# waga_can.net
KiCad netlist of a schematic drawn in EAGLE
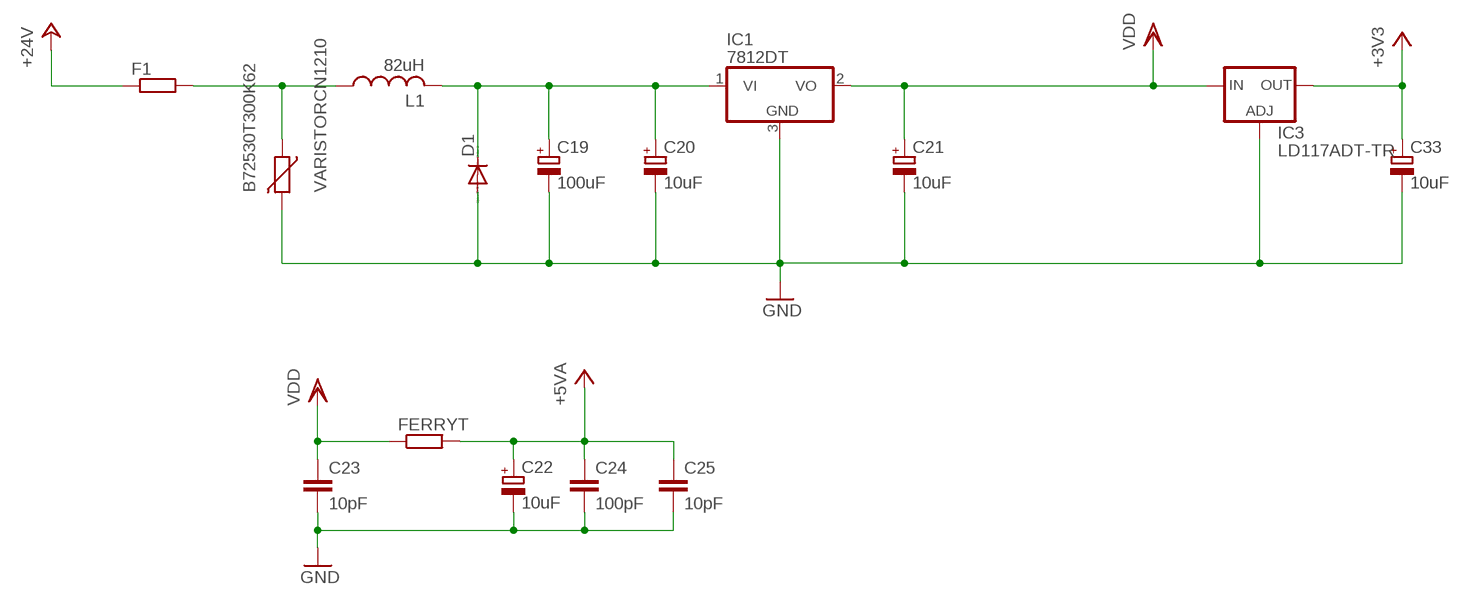
[diagram p0: schematic, sheet 1]
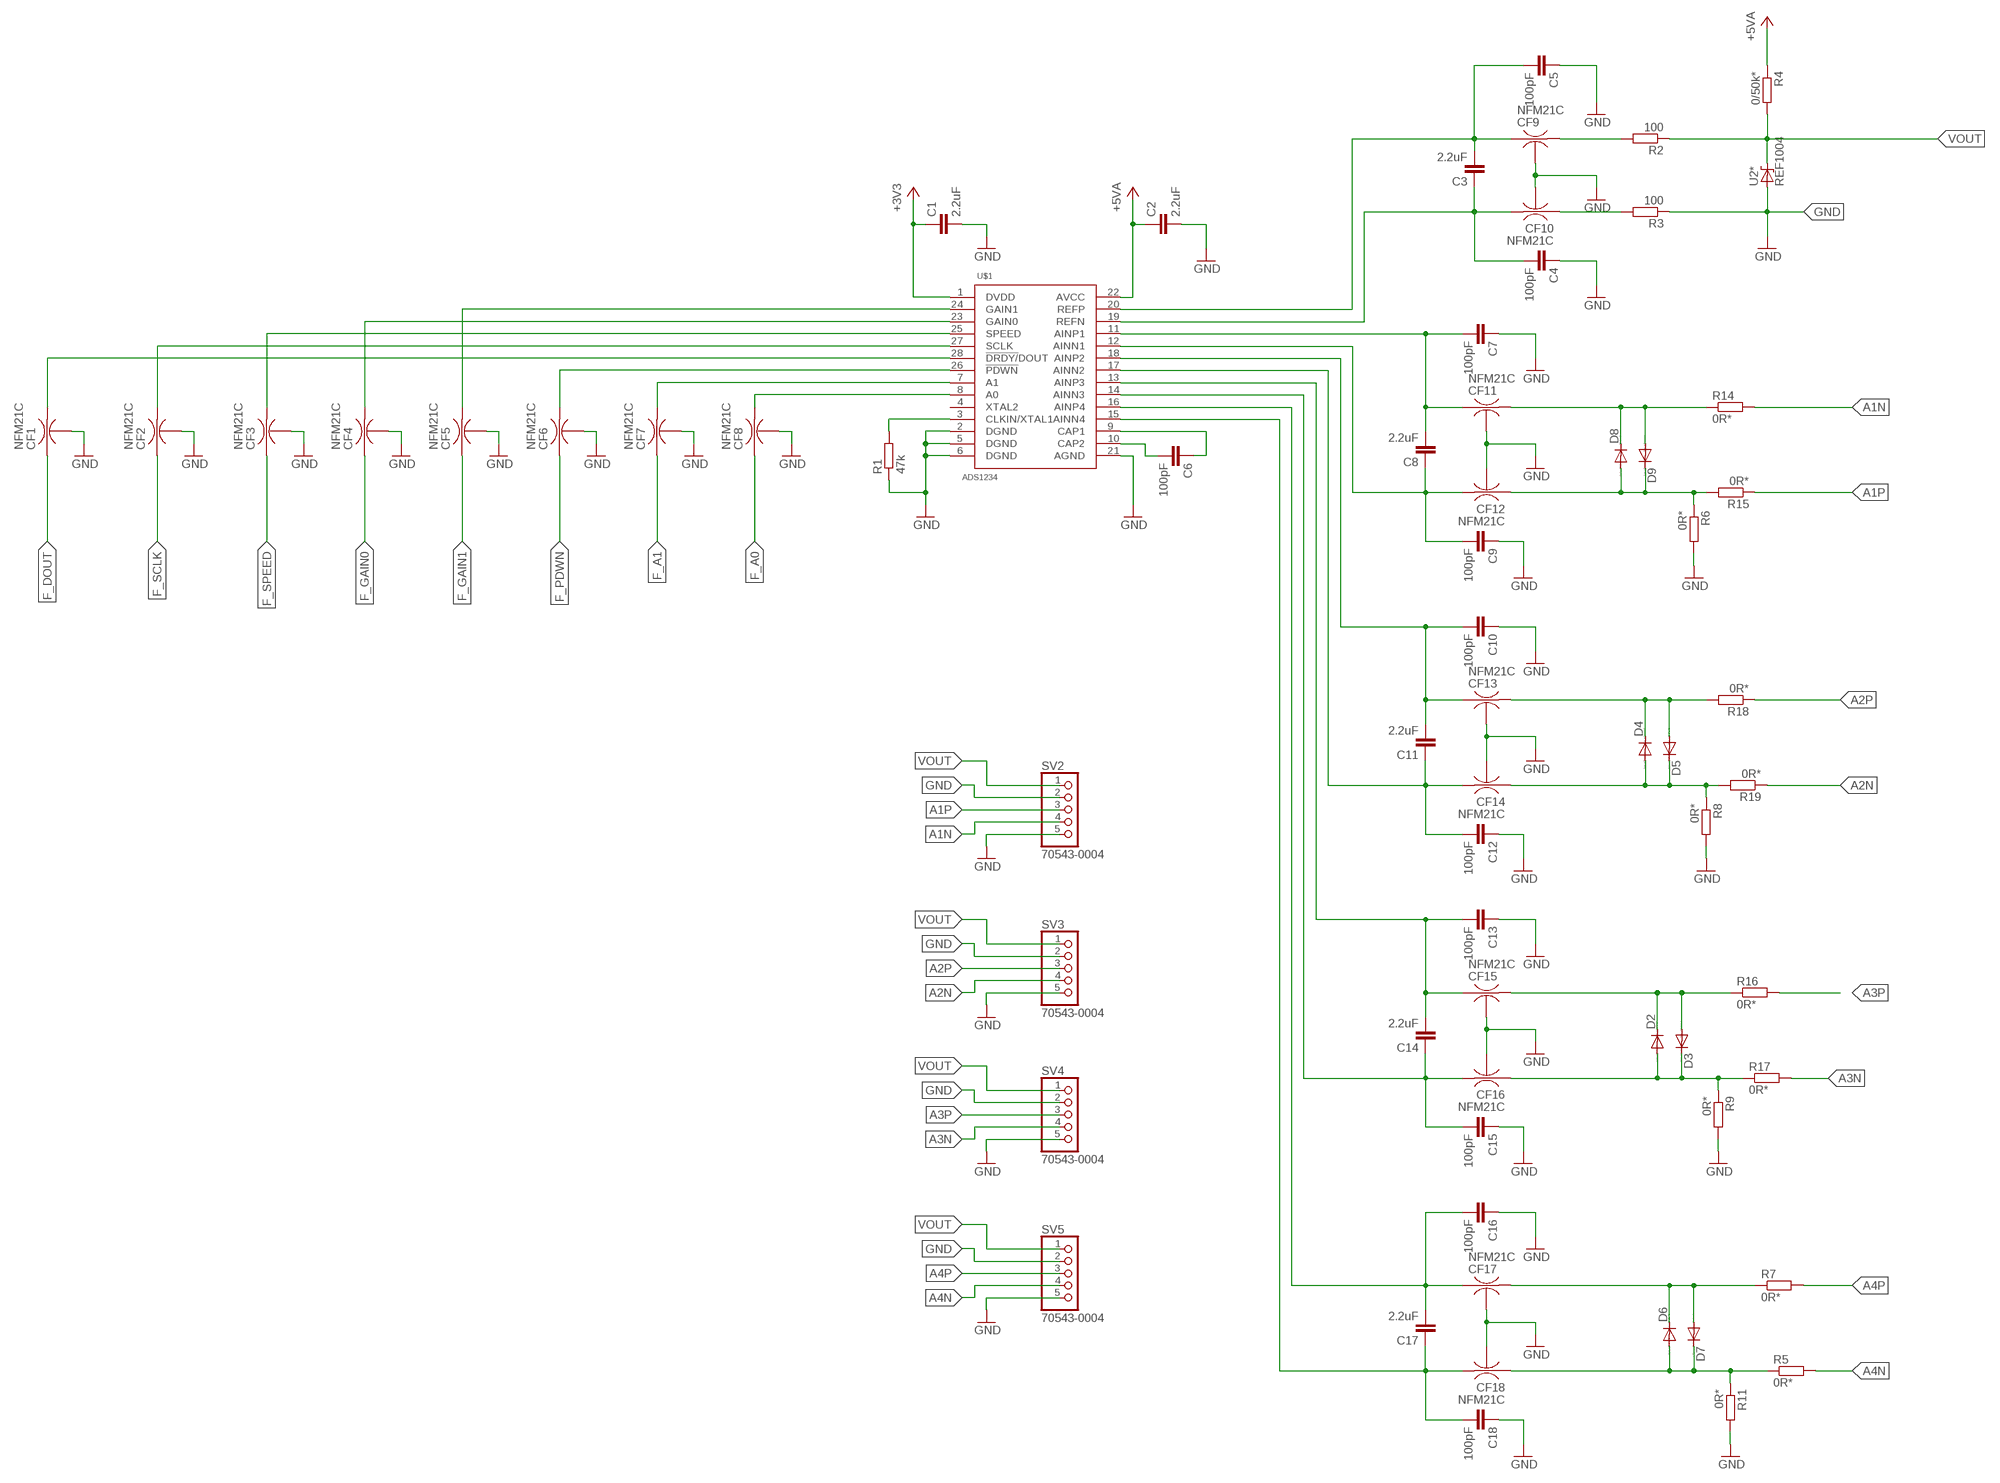
[diagram p1: schematic, sheet 2, part 1 of 2]
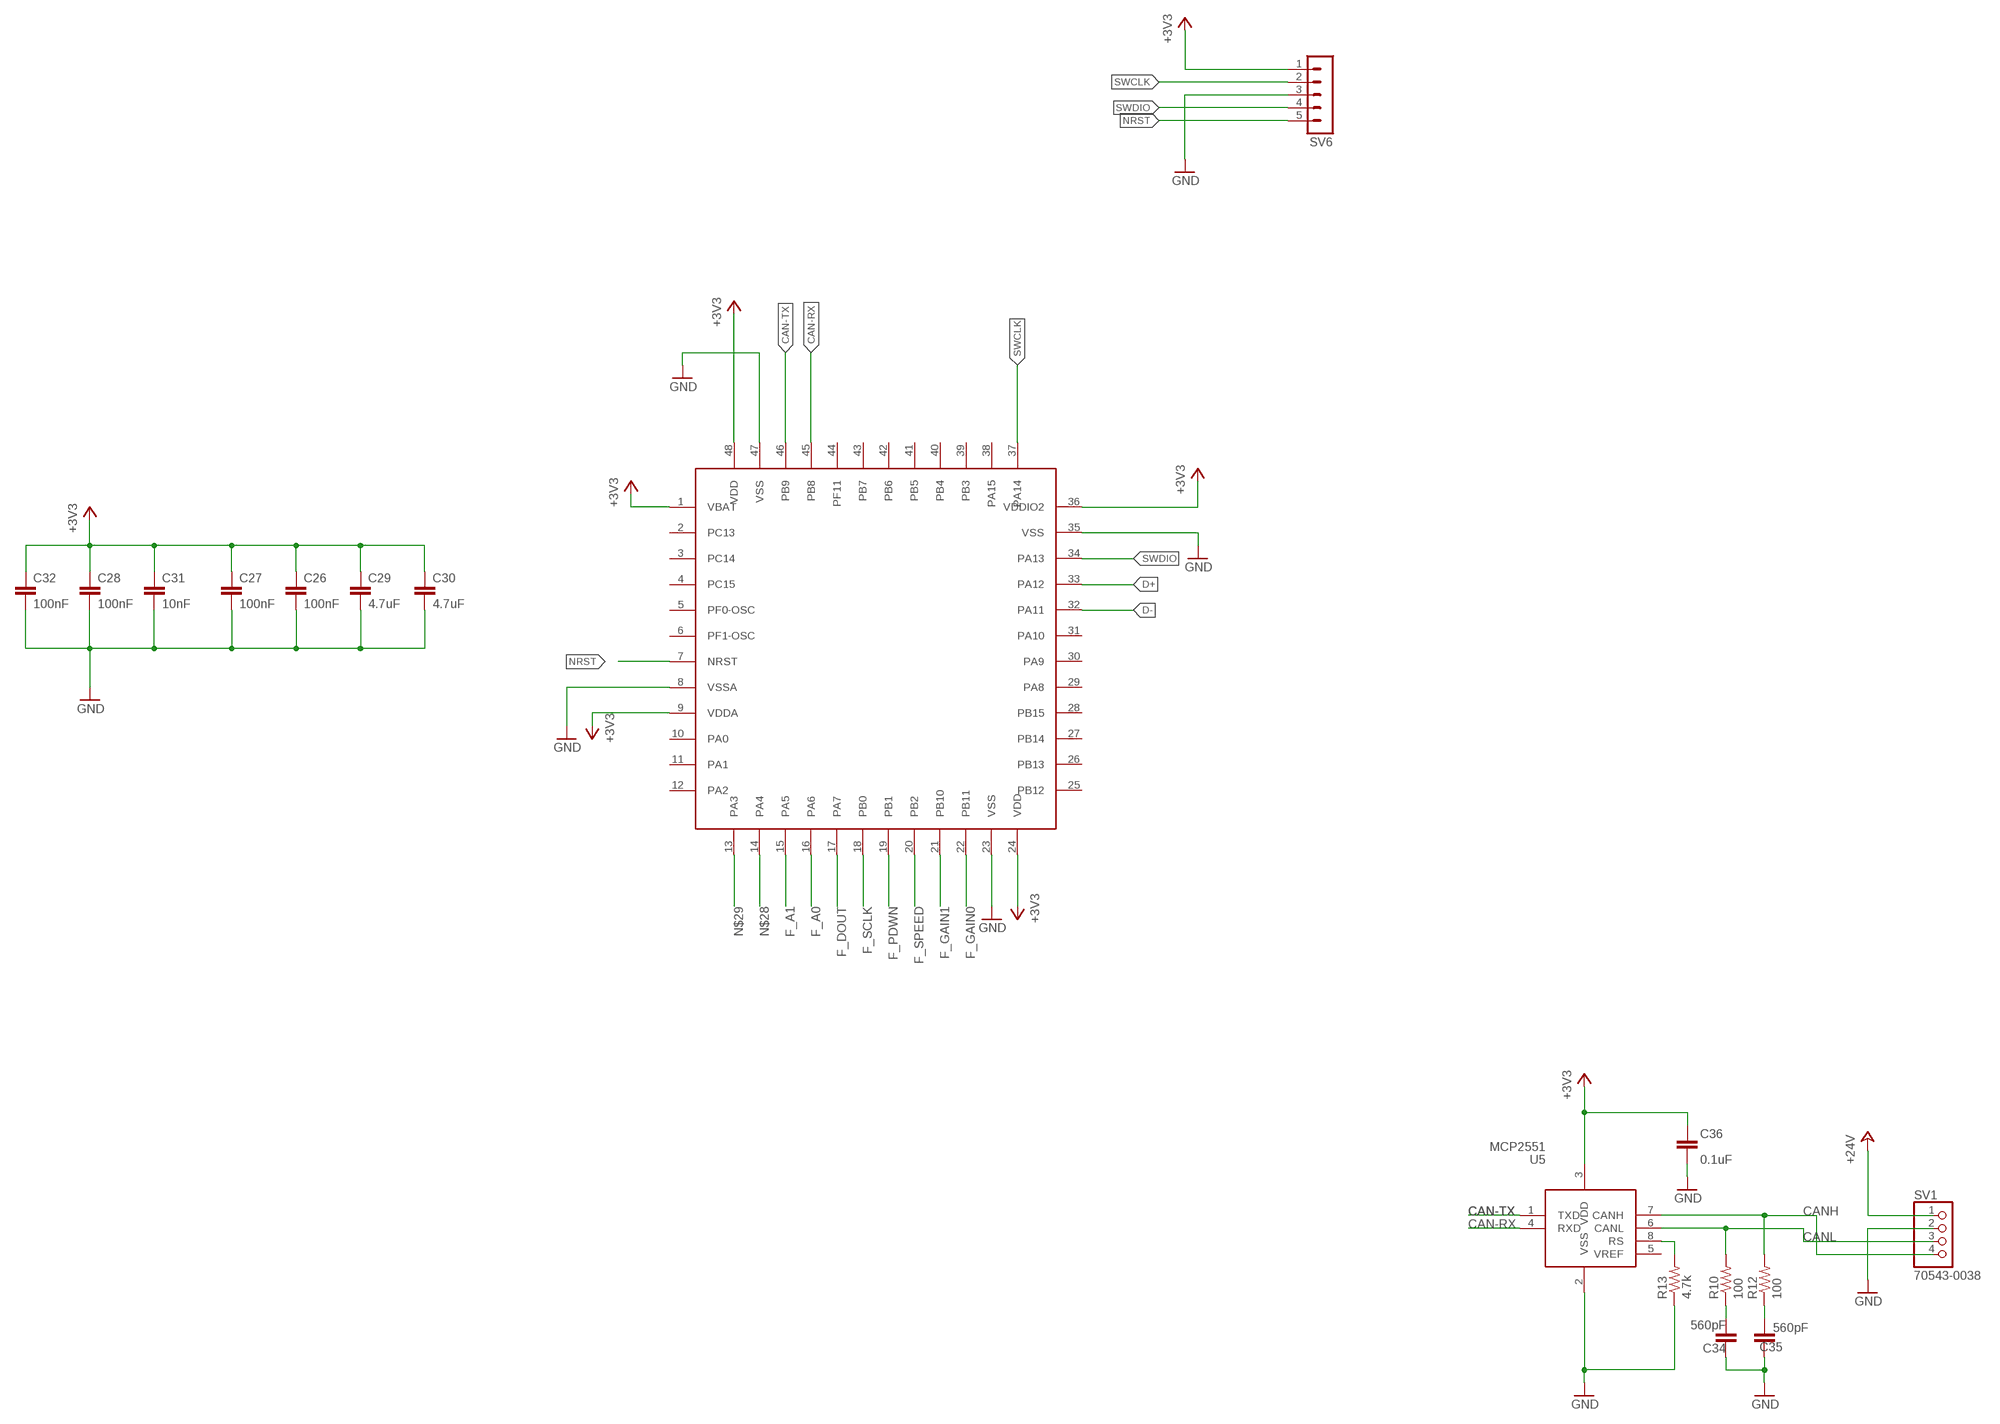
[diagram p2: schematic, sheet 2, part 2 of 2]

(export (version "E")
  (design (tool "Eeschema 10.0.6"))
  (components
    (comp (ref "C1")
      (value "2.2uF")
      (footprint "eagle-import:C0805K")
      (libsource (lib "eagle-import") (part "C-EUC0805K"))
    )
    (comp (ref "C2")
      (value "2.2uF")
      (footprint "eagle-import:C0805K")
      (libsource (lib "eagle-import") (part "C-EUC0805K"))
    )
    (comp (ref "C3")
      (value "2.2uF")
      (footprint "eagle-import:C0805K")
      (libsource (lib "eagle-import") (part "C-EUC0805K"))
    )
    (comp (ref "C4")
      (value "100pF")
      (footprint "eagle-import:C0805K")
      (libsource (lib "eagle-import") (part "C-EUC0805K"))
    )
    (comp (ref "C5")
      (value "100pF")
      (footprint "eagle-import:C0805K")
      (libsource (lib "eagle-import") (part "C-EUC0805K"))
    )
    (comp (ref "C6")
      (value "100pF")
      (footprint "eagle-import:C0805K")
      (libsource (lib "eagle-import") (part "C-EUC0805K"))
    )
    (comp (ref "C7")
      (value "100pF")
      (footprint "eagle-import:C0805K")
      (libsource (lib "eagle-import") (part "C-EUC0805K"))
    )
    (comp (ref "C8")
      (value "2.2uF")
      (footprint "eagle-import:C0805K")
      (libsource (lib "eagle-import") (part "C-EUC0805K"))
    )
    (comp (ref "C9")
      (value "100pF")
      (footprint "eagle-import:C0805K")
      (libsource (lib "eagle-import") (part "C-EUC0805K"))
    )
    (comp (ref "C10")
      (value "100pF")
      (footprint "eagle-import:C0805K")
      (libsource (lib "eagle-import") (part "C-EUC0805K"))
    )
    (comp (ref "C11")
      (value "2.2uF")
      (footprint "eagle-import:C0805K")
      (libsource (lib "eagle-import") (part "C-EUC0805K"))
    )
    (comp (ref "C12")
      (value "100pF")
      (footprint "eagle-import:C0805K")
      (libsource (lib "eagle-import") (part "C-EUC0805K"))
    )
    (comp (ref "C13")
      (value "100pF")
      (footprint "eagle-import:C0805K")
      (libsource (lib "eagle-import") (part "C-EUC0805K"))
    )
    (comp (ref "C14")
      (value "2.2uF")
      (footprint "eagle-import:C0805K")
      (libsource (lib "eagle-import") (part "C-EUC0805K"))
    )
    (comp (ref "C15")
      (value "100pF")
      (footprint "eagle-import:C0805K")
      (libsource (lib "eagle-import") (part "C-EUC0805K"))
    )
    (comp (ref "C16")
      (value "100pF")
      (footprint "eagle-import:C0805K")
      (libsource (lib "eagle-import") (part "C-EUC0805K"))
    )
    (comp (ref "C17")
      (value "2.2uF")
      (footprint "eagle-import:C0805K")
      (libsource (lib "eagle-import") (part "C-EUC0805K"))
    )
    (comp (ref "C18")
      (value "100pF")
      (footprint "eagle-import:C0805K")
      (libsource (lib "eagle-import") (part "C-EUC0805K"))
    )
    (comp (ref "C26")
      (value "100nF")
      (footprint "eagle-import:C0603")
      (libsource (lib "eagle-import") (part "C-EUC0603"))
    )
    (comp (ref "C27")
      (value "100nF")
      (footprint "eagle-import:C0603")
      (libsource (lib "eagle-import") (part "C-EUC0603"))
    )
    (comp (ref "C28")
      (value "100nF")
      (footprint "eagle-import:C0603")
      (libsource (lib "eagle-import") (part "C-EUC0603"))
    )
    (comp (ref "C29")
      (value "4.7uF")
      (footprint "eagle-import:C0603")
      (libsource (lib "eagle-import") (part "C-EUC0603"))
    )
    (comp (ref "C30")
      (value "4.7uF")
      (footprint "eagle-import:C0603")
      (libsource (lib "eagle-import") (part "C-EUC0603"))
    )
    (comp (ref "C31")
      (value "10nF")
      (footprint "eagle-import:C0603")
      (libsource (lib "eagle-import") (part "C-EUC0603"))
    )
    (comp (ref "C32")
      (value "100nF")
      (footprint "eagle-import:C0603")
      (libsource (lib "eagle-import") (part "C-EUC0603"))
    )
    (comp (ref "C34")
      (value "560pF")
      (footprint "eagle-import:0603-CAP")
      (libsource (lib "eagle-import") (part "CAP0603-CAP"))
    )
    (comp (ref "C35")
      (value "560pF")
      (footprint "eagle-import:0603-CAP")
      (libsource (lib "eagle-import") (part "CAP0603-CAP"))
    )
    (comp (ref "C36")
      (value "0.1uF")
      (footprint "eagle-import:0603-CAP")
      (libsource (lib "eagle-import") (part "CAP0603-CAP"))
    )
    (comp (ref "CF1")
      (value "NFM21C")
      (footprint "eagle-import:NFM21C")
      (fields (field (name "MPN") "NFM21CC102R1H3D"))
      (libsource (lib "eagle-import") (part "NFM21C"))
    )
    (comp (ref "CF2")
      (value "NFM21C")
      (footprint "eagle-import:NFM21C")
      (fields (field (name "MPN") "NFM21CC102R1H3D"))
      (libsource (lib "eagle-import") (part "NFM21C"))
    )
    (comp (ref "CF3")
      (value "NFM21C")
      (footprint "eagle-import:NFM21C")
      (fields (field (name "MPN") "NFM21CC102R1H3D"))
      (libsource (lib "eagle-import") (part "NFM21C"))
    )
    (comp (ref "CF4")
      (value "NFM21C")
      (footprint "eagle-import:NFM21C")
      (fields (field (name "MPN") "NFM21CC102R1H3D"))
      (libsource (lib "eagle-import") (part "NFM21C"))
    )
    (comp (ref "CF5")
      (value "NFM21C")
      (footprint "eagle-import:NFM21C")
      (fields (field (name "MPN") "NFM21CC102R1H3D"))
      (libsource (lib "eagle-import") (part "NFM21C"))
    )
    (comp (ref "CF6")
      (value "NFM21C")
      (footprint "eagle-import:NFM21C")
      (fields (field (name "MPN") "NFM21CC102R1H3D"))
      (libsource (lib "eagle-import") (part "NFM21C"))
    )
    (comp (ref "CF7")
      (value "NFM21C")
      (footprint "eagle-import:NFM21C")
      (fields (field (name "MPN") "NFM21CC102R1H3D"))
      (libsource (lib "eagle-import") (part "NFM21C"))
    )
    (comp (ref "CF8")
      (value "NFM21C")
      (footprint "eagle-import:NFM21C")
      (fields (field (name "MPN") "NFM21CC102R1H3D"))
      (libsource (lib "eagle-import") (part "NFM21C"))
    )
    (comp (ref "CF9")
      (value "NFM21C")
      (footprint "eagle-import:NFM21C")
      (fields (field (name "MPN") "NFM21CC102R1H3D"))
      (libsource (lib "eagle-import") (part "NFM21C"))
    )
    (comp (ref "CF10")
      (value "NFM21C")
      (footprint "eagle-import:NFM21C")
      (fields (field (name "MPN") "NFM21CC102R1H3D"))
      (libsource (lib "eagle-import") (part "NFM21C"))
    )
    (comp (ref "CF11")
      (value "NFM21C")
      (footprint "eagle-import:NFM21C")
      (fields (field (name "MPN") "NFM21CC102R1H3D"))
      (libsource (lib "eagle-import") (part "NFM21C"))
    )
    (comp (ref "CF12")
      (value "NFM21C")
      (footprint "eagle-import:NFM21C")
      (fields (field (name "MPN") "NFM21CC102R1H3D"))
      (libsource (lib "eagle-import") (part "NFM21C"))
    )
    (comp (ref "CF13")
      (value "NFM21C")
      (footprint "eagle-import:NFM21C")
      (fields (field (name "MPN") "NFM21CC102R1H3D"))
      (libsource (lib "eagle-import") (part "NFM21C"))
    )
    (comp (ref "CF14")
      (value "NFM21C")
      (footprint "eagle-import:NFM21C")
      (fields (field (name "MPN") "NFM21CC102R1H3D"))
      (libsource (lib "eagle-import") (part "NFM21C"))
    )
    (comp (ref "CF15")
      (value "NFM21C")
      (footprint "eagle-import:NFM21C")
      (fields (field (name "MPN") "NFM21CC102R1H3D"))
      (libsource (lib "eagle-import") (part "NFM21C"))
    )
    (comp (ref "CF16")
      (value "NFM21C")
      (footprint "eagle-import:NFM21C")
      (fields (field (name "MPN") "NFM21CC102R1H3D"))
      (libsource (lib "eagle-import") (part "NFM21C"))
    )
    (comp (ref "CF17")
      (value "NFM21C")
      (footprint "eagle-import:NFM21C")
      (fields (field (name "MPN") "NFM21CC102R1H3D"))
      (libsource (lib "eagle-import") (part "NFM21C"))
    )
    (comp (ref "CF18")
      (value "NFM21C")
      (footprint "eagle-import:NFM21C")
      (fields (field (name "MPN") "NFM21CC102R1H3D"))
      (libsource (lib "eagle-import") (part "NFM21C"))
    )
    (comp (ref "D2")
      (value "DIODE-MICROMELF-W")
      (footprint "eagle-import:MICROMELF-W")
      (libsource (lib "eagle-import") (part "DIODE-MICROMELF-W"))
    )
    (comp (ref "D3")
      (value "DIODE-MICROMELF-W")
      (footprint "eagle-import:MICROMELF-W")
      (libsource (lib "eagle-import") (part "DIODE-MICROMELF-W"))
    )
    (comp (ref "D4")
      (value "DIODE-MICROMELF-W")
      (footprint "eagle-import:MICROMELF-W")
      (libsource (lib "eagle-import") (part "DIODE-MICROMELF-W"))
    )
    (comp (ref "D5")
      (value "DIODE-MICROMELF-W")
      (footprint "eagle-import:MICROMELF-W")
      (libsource (lib "eagle-import") (part "DIODE-MICROMELF-W"))
    )
    (comp (ref "D6")
      (value "DIODE-MICROMELF-W")
      (footprint "eagle-import:MICROMELF-W")
      (libsource (lib "eagle-import") (part "DIODE-MICROMELF-W"))
    )
    (comp (ref "D7")
      (value "DIODE-MICROMELF-W")
      (footprint "eagle-import:MICROMELF-W")
      (libsource (lib "eagle-import") (part "DIODE-MICROMELF-W"))
    )
    (comp (ref "D8")
      (value "DIODE-MICROMELF-W")
      (footprint "eagle-import:MICROMELF-W")
      (libsource (lib "eagle-import") (part "DIODE-MICROMELF-W"))
    )
    (comp (ref "D9")
      (value "DIODE-MICROMELF-W")
      (footprint "eagle-import:MICROMELF-W")
      (libsource (lib "eagle-import") (part "DIODE-MICROMELF-W"))
    )
    (comp (ref "R1")
      (value "47k")
      (footprint "eagle-import:R0805")
      (libsource (lib "eagle-import") (part "R-EU_R0805"))
    )
    (comp (ref "R2")
      (value "100")
      (footprint "eagle-import:R0805")
      (libsource (lib "eagle-import") (part "R-EU_R0805"))
    )
    (comp (ref "R3")
      (value "100")
      (footprint "eagle-import:R0805")
      (libsource (lib "eagle-import") (part "R-EU_R0805"))
    )
    (comp (ref "R4")
      (value "0/50k*")
      (footprint "eagle-import:R0805")
      (libsource (lib "eagle-import") (part "R-EU_R0805"))
    )
    (comp (ref "R5")
      (value "0R*")
      (footprint "eagle-import:R0603")
      (libsource (lib "eagle-import") (part "R-EU_R0603"))
    )
    (comp (ref "R6")
      (value "0R*")
      (footprint "eagle-import:R0603")
      (libsource (lib "eagle-import") (part "R-EU_R0603"))
    )
    (comp (ref "R7")
      (value "0R*")
      (footprint "eagle-import:R0603")
      (libsource (lib "eagle-import") (part "R-EU_R0603"))
    )
    (comp (ref "R8")
      (value "0R*")
      (footprint "eagle-import:R0603")
      (libsource (lib "eagle-import") (part "R-EU_R0603"))
    )
    (comp (ref "R9")
      (value "0R*")
      (footprint "eagle-import:R0603")
      (libsource (lib "eagle-import") (part "R-EU_R0603"))
    )
    (comp (ref "R10")
      (value "100")
      (footprint "eagle-import:0603-RES")
      (libsource (lib "eagle-import") (part "RESISTOR0603-RES"))
    )
    (comp (ref "R11")
      (value "0R*")
      (footprint "eagle-import:R0603")
      (libsource (lib "eagle-import") (part "R-EU_R0603"))
    )
    (comp (ref "R12")
      (value "100")
      (footprint "eagle-import:0603-RES")
      (libsource (lib "eagle-import") (part "RESISTOR0603-RES"))
    )
    (comp (ref "R13")
      (value "4.7k")
      (footprint "eagle-import:0603-RES")
      (libsource (lib "eagle-import") (part "RESISTOR0603-RES"))
    )
    (comp (ref "R14")
      (value "0R*")
      (footprint "eagle-import:R0603")
      (libsource (lib "eagle-import") (part "R-EU_R0603"))
    )
    (comp (ref "R15")
      (value "0R*")
      (footprint "eagle-import:R0603")
      (libsource (lib "eagle-import") (part "R-EU_R0603"))
    )
    (comp (ref "R16")
      (value "0R*")
      (footprint "eagle-import:R0603")
      (libsource (lib "eagle-import") (part "R-EU_R0603"))
    )
    (comp (ref "R17")
      (value "0R*")
      (footprint "eagle-import:R0603")
      (libsource (lib "eagle-import") (part "R-EU_R0603"))
    )
    (comp (ref "R18")
      (value "0R*")
      (footprint "eagle-import:R0603")
      (libsource (lib "eagle-import") (part "R-EU_R0603"))
    )
    (comp (ref "R19")
      (value "0R*")
      (footprint "eagle-import:R0603")
      (libsource (lib "eagle-import") (part "R-EU_R0603"))
    )
    (comp (ref "SV1")
      (value "70543-0038")
      (footprint "eagle-import:70543-0038")
      (libsource (lib "eagle-import") (part "70543-0038"))
    )
    (comp (ref "SV2")
      (value "70543-0004")
      (footprint "eagle-import:70543-0004")
      (libsource (lib "eagle-import") (part "70543-0004"))
    )
    (comp (ref "SV3")
      (value "70543-0004")
      (footprint "eagle-import:70543-0004")
      (libsource (lib "eagle-import") (part "70543-0004"))
    )
    (comp (ref "SV4")
      (value "70543-0004")
      (footprint "eagle-import:70543-0004")
      (libsource (lib "eagle-import") (part "70543-0004"))
    )
    (comp (ref "SV5")
      (value "70543-0004")
      (footprint "eagle-import:70543-0004")
      (libsource (lib "eagle-import") (part "70543-0004"))
    )
    (comp (ref "SV6")
      (value "MA05-1")
      (footprint "eagle-import:MA05-1")
      (libsource (lib "eagle-import") (part "MA05-1"))
    )
    (comp (ref "U$1")
      (value "ADS1234")
      (footprint "eagle-import:TSSOP-28")
      (libsource (lib "eagle-import") (part "ADS1234"))
    )
    (comp (ref "U$2")
      (value "STM32F42C6T6")
      (footprint "eagle-import:LQFP48")
      (libsource (lib "eagle-import") (part "STM32F42C6T6"))
    )
    (comp (ref "U2*")
      (value "REF1004")
      (footprint "eagle-import:SO8")
      (libsource (lib "eagle-import") (part "REF1004"))
    )
    (comp (ref "U5")
      (value "MCP2551")
      (footprint "eagle-import:SO-08M")
      (libsource (lib "eagle-import") (part "MCP2551"))
    )
    (comp (ref "B72530T300K62")
      (value "VARISTORCN1210")
      (footprint "eagle-import:CT_CN1210")
      (libsource (lib "eagle-import") (part "VARISTORCN1210"))
    )
    (comp (ref "C19")
      (value "100uF")
      (footprint "eagle-import:153CLV-0810")
      (libsource (lib "eagle-import") (part "CPOL-EU153CLV-0810"))
    )
    (comp (ref "C20")
      (value "10uF")
      (footprint "eagle-import:153CLV-0605")
      (libsource (lib "eagle-import") (part "CPOL-EU153CLV-0605"))
    )
    (comp (ref "C21")
      (value "10uF")
      (footprint "eagle-import:153CLV-0605")
      (libsource (lib "eagle-import") (part "CPOL-EU153CLV-0605"))
    )
    (comp (ref "C22")
      (value "10uF")
      (footprint "eagle-import:153CLV-0605")
      (libsource (lib "eagle-import") (part "CPOL-EU153CLV-0605"))
    )
    (comp (ref "C23")
      (value "10pF")
      (footprint "eagle-import:C0805")
      (libsource (lib "eagle-import") (part "C-EUC0805"))
    )
    (comp (ref "C24")
      (value "100pF")
      (footprint "eagle-import:C0805")
      (libsource (lib "eagle-import") (part "C-EUC0805"))
    )
    (comp (ref "C25")
      (value "10pF")
      (footprint "eagle-import:C0805")
      (libsource (lib "eagle-import") (part "C-EUC0805"))
    )
    (comp (ref "C33")
      (value "10uF")
      (footprint "eagle-import:153CLV-0605")
      (libsource (lib "eagle-import") (part "CPOL-EU153CLV-0605"))
    )
    (comp (ref "D1")
      (value "DIODE-SMB")
      (footprint "eagle-import:SMB")
      (libsource (lib "eagle-import") (part "DIODE-SMB"))
    )
    (comp (ref "F1")
      (value "R-EU_1812X7R")
      (footprint "eagle-import:1812X7R")
      (libsource (lib "eagle-import") (part "R-EU_1812X7R"))
    )
    (comp (ref "FERRYT")
      (value "R-EU_M0805")
      (footprint "eagle-import:M0805")
      (libsource (lib "eagle-import") (part "R-EU_M0805"))
    )
    (comp (ref "IC1")
      (value "7812DT")
      (footprint "eagle-import:TO252")
      (libsource (lib "eagle-import") (part "78DT12"))
    )
    (comp (ref "IC3")
      (value "LD117ADT-TR")
      (footprint "eagle-import:DPACK")
      (libsource (lib "eagle-import") (part "LD117A?DT-TR"))
    )
    (comp (ref "L1")
      (value "82uH")
      (footprint "eagle-import:L4532P")
      (libsource (lib "eagle-import") (part "L-USL4532P"))
    )
  )
  (nets
    (net (code "1") (name "+3V3") (class "Default")
      (node (ref "C1") (pin "1") (pinfunction "1_1") (pintype "passive"))
      (node (ref "C26") (pin "1") (pinfunction "1_1") (pintype "passive"))
      (node (ref "C27") (pin "1") (pinfunction "1_1") (pintype "passive"))
      (node (ref "C28") (pin "1") (pinfunction "1_1") (pintype "passive"))
      (node (ref "C29") (pin "1") (pinfunction "1_1") (pintype "passive"))
      (node (ref "C30") (pin "1") (pinfunction "1_1") (pintype "passive"))
      (node (ref "C31") (pin "1") (pinfunction "1_1") (pintype "passive"))
      (node (ref "C32") (pin "1") (pinfunction "1_1") (pintype "passive"))
      (node (ref "C33") (pin "+") (pinfunction "+_+") (pintype "passive"))
      (node (ref "C36") (pin "2") (pinfunction "2_2") (pintype "passive"))
      (node (ref "IC3") (pin "4") (pinfunction "OUT_4") (pintype "passive"))
      (node (ref "SV6") (pin "1") (pinfunction "1_1") (pintype "passive"))
      (node (ref "U$1") (pin "1") (pinfunction "DVDD_1") (pintype "bidirectional"))
      (node (ref "U$2") (pin "1") (pinfunction "VBAT_1") (pintype "bidirectional"))
      (node (ref "U$2") (pin "24") (pinfunction "VDD_24") (pintype "bidirectional"))
      (node (ref "U$2") (pin "36") (pinfunction "VDDIO2_36") (pintype "bidirectional"))
      (node (ref "U$2") (pin "48") (pinfunction "VDD_48") (pintype "bidirectional"))
      (node (ref "U$2") (pin "9") (pinfunction "VDDA_9") (pintype "bidirectional"))
      (node (ref "U5") (pin "3") (pinfunction "VDD_3") (pintype "power_in"))
    )
    (net (code "2") (name "+5V") (class "Default")
      (node (ref "C2") (pin "1") (pinfunction "1_1") (pintype "passive"))
      (node (ref "C22") (pin "+") (pinfunction "+_+") (pintype "passive"))
      (node (ref "C24") (pin "1") (pinfunction "1_1") (pintype "passive"))
      (node (ref "C25") (pin "1") (pinfunction "1_1") (pintype "passive"))
      (node (ref "FERRYT") (pin "2") (pinfunction "2_2") (pintype "passive"))
      (node (ref "R4") (pin "1") (pinfunction "1_1") (pintype "passive"))
      (node (ref "U$1") (pin "22") (pinfunction "AVCC_22") (pintype "bidirectional"))
    )
    (net (code "3") (name "+24V") (class "Default")
      (node (ref "F1") (pin "1") (pinfunction "1_1") (pintype "passive"))
      (node (ref "SV1") (pin "1") (pinfunction "1_1") (pintype "passive"))
    )
    (net (code "4") (name "A1N") (class "Default")
      (node (ref "R14") (pin "2") (pinfunction "2_2") (pintype "passive"))
      (node (ref "SV2") (pin "4") (pinfunction "4_4") (pintype "passive"))
    )
    (net (code "5") (name "A1P") (class "Default")
      (node (ref "R15") (pin "1") (pinfunction "1_1") (pintype "passive"))
      (node (ref "SV2") (pin "3") (pinfunction "3_3") (pintype "passive"))
    )
    (net (code "6") (name "A2N") (class "Default")
      (node (ref "R19") (pin "1") (pinfunction "1_1") (pintype "passive"))
      (node (ref "SV3") (pin "4") (pinfunction "4_4") (pintype "passive"))
    )
    (net (code "7") (name "A2P") (class "Default")
      (node (ref "R18") (pin "1") (pinfunction "1_1") (pintype "passive"))
      (node (ref "SV3") (pin "3") (pinfunction "3_3") (pintype "passive"))
    )
    (net (code "8") (name "A3N") (class "Default")
      (node (ref "R17") (pin "2") (pinfunction "2_2") (pintype "passive"))
      (node (ref "SV4") (pin "4") (pinfunction "4_4") (pintype "passive"))
    )
    (net (code "9") (name "A3P") (class "Default")
      (node (ref "R16") (pin "2") (pinfunction "2_2") (pintype "passive"))
      (node (ref "SV4") (pin "3") (pinfunction "3_3") (pintype "passive"))
    )
    (net (code "10") (name "A4N") (class "Default")
      (node (ref "R5") (pin "2") (pinfunction "2_2") (pintype "passive"))
      (node (ref "SV5") (pin "4") (pinfunction "4_4") (pintype "passive"))
    )
    (net (code "11") (name "A4P") (class "Default")
      (node (ref "R7") (pin "2") (pinfunction "2_2") (pintype "passive"))
      (node (ref "SV5") (pin "3") (pinfunction "3_3") (pintype "passive"))
    )
    (net (code "12") (name "CAN-RX") (class "Default")
      (node (ref "U$2") (pin "45") (pinfunction "PB8_45") (pintype "bidirectional"))
      (node (ref "U5") (pin "4") (pinfunction "RXD_4") (pintype "bidirectional"))
    )
    (net (code "13") (name "CAN-TX") (class "Default")
      (node (ref "U$2") (pin "46") (pinfunction "PB9_46") (pintype "bidirectional"))
      (node (ref "U5") (pin "1") (pinfunction "TXD_1") (pintype "bidirectional"))
    )
    (net (code "14") (name "CANH") (class "Default")
      (node (ref "R12") (pin "2") (pinfunction "2_2") (pintype "passive"))
      (node (ref "SV1") (pin "4") (pinfunction "4_4") (pintype "passive"))
      (node (ref "U5") (pin "7") (pinfunction "CANH_7") (pintype "bidirectional"))
    )
    (net (code "15") (name "CANL") (class "Default")
      (node (ref "R10") (pin "2") (pinfunction "2_2") (pintype "passive"))
      (node (ref "SV1") (pin "3") (pinfunction "3_3") (pintype "passive"))
      (node (ref "U5") (pin "6") (pinfunction "CANL_6") (pintype "bidirectional"))
    )
    (net (code "16") (name "D+") (class "Default")
      (node (ref "U$2") (pin "33") (pinfunction "PA12_33") (pintype "bidirectional"))
    )
    (net (code "17") (name "D-") (class "Default")
      (node (ref "U$2") (pin "32") (pinfunction "PA11_32") (pintype "bidirectional"))
    )
    (net (code "18") (name "F_A0") (class "Default")
      (node (ref "CF8") (pin "1") (pinfunction "1_1") (pintype "passive"))
      (node (ref "U$2") (pin "16") (pinfunction "PA6_16") (pintype "bidirectional"))
    )
    (net (code "19") (name "F_A1") (class "Default")
      (node (ref "CF7") (pin "1") (pinfunction "1_1") (pintype "passive"))
      (node (ref "U$2") (pin "15") (pinfunction "PA5_15") (pintype "bidirectional"))
    )
    (net (code "20") (name "F_DOUT") (class "Default")
      (node (ref "CF1") (pin "1") (pinfunction "1_1") (pintype "passive"))
      (node (ref "U$2") (pin "17") (pinfunction "PA7_17") (pintype "bidirectional"))
    )
    (net (code "21") (name "F_GAIN0") (class "Default")
      (node (ref "CF4") (pin "1") (pinfunction "1_1") (pintype "passive"))
      (node (ref "U$2") (pin "22") (pinfunction "PB11_22") (pintype "bidirectional"))
    )
    (net (code "22") (name "F_GAIN1") (class "Default")
      (node (ref "CF5") (pin "1") (pinfunction "1_1") (pintype "passive"))
      (node (ref "U$2") (pin "21") (pinfunction "PB10_21") (pintype "bidirectional"))
    )
    (net (code "23") (name "F_PDWN") (class "Default")
      (node (ref "CF6") (pin "1") (pinfunction "1_1") (pintype "passive"))
      (node (ref "U$2") (pin "19") (pinfunction "PB1_19") (pintype "bidirectional"))
    )
    (net (code "24") (name "F_SCLK") (class "Default")
      (node (ref "CF2") (pin "1") (pinfunction "1_1") (pintype "passive"))
      (node (ref "U$2") (pin "18") (pinfunction "PB0_18") (pintype "bidirectional"))
    )
    (net (code "25") (name "F_SPEED") (class "Default")
      (node (ref "CF3") (pin "1") (pinfunction "1_1") (pintype "passive"))
      (node (ref "U$2") (pin "20") (pinfunction "PB2_20") (pintype "bidirectional"))
    )
    (net (code "26") (name "GND") (class "Default")
      (node (ref "B72530T300K62") (pin "2") (pinfunction "2_2") (pintype "passive"))
      (node (ref "C1") (pin "2") (pinfunction "2_2") (pintype "passive"))
      (node (ref "C10") (pin "1") (pinfunction "1_1") (pintype "passive"))
      (node (ref "C12") (pin "1") (pinfunction "1_1") (pintype "passive"))
      (node (ref "C13") (pin "1") (pinfunction "1_1") (pintype "passive"))
      (node (ref "C15") (pin "1") (pinfunction "1_1") (pintype "passive"))
      (node (ref "C16") (pin "1") (pinfunction "1_1") (pintype "passive"))
      (node (ref "C18") (pin "1") (pinfunction "1_1") (pintype "passive"))
      (node (ref "C19") (pin "-") (pinfunction "-_-") (pintype "passive"))
      (node (ref "C2") (pin "2") (pinfunction "2_2") (pintype "passive"))
      (node (ref "C20") (pin "-") (pinfunction "-_-") (pintype "passive"))
      (node (ref "C21") (pin "-") (pinfunction "-_-") (pintype "passive"))
      (node (ref "C22") (pin "-") (pinfunction "-_-") (pintype "passive"))
      (node (ref "C23") (pin "2") (pinfunction "2_2") (pintype "passive"))
      (node (ref "C24") (pin "2") (pinfunction "2_2") (pintype "passive"))
      (node (ref "C25") (pin "2") (pinfunction "2_2") (pintype "passive"))
      (node (ref "C26") (pin "2") (pinfunction "2_2") (pintype "passive"))
      (node (ref "C27") (pin "2") (pinfunction "2_2") (pintype "passive"))
      (node (ref "C28") (pin "2") (pinfunction "2_2") (pintype "passive"))
      (node (ref "C29") (pin "2") (pinfunction "2_2") (pintype "passive"))
      (node (ref "C30") (pin "2") (pinfunction "2_2") (pintype "passive"))
      (node (ref "C31") (pin "2") (pinfunction "2_2") (pintype "passive"))
      (node (ref "C32") (pin "2") (pinfunction "2_2") (pintype "passive"))
      (node (ref "C33") (pin "-") (pinfunction "-_-") (pintype "passive"))
      (node (ref "C34") (pin "1") (pinfunction "1_1") (pintype "passive"))
      (node (ref "C35") (pin "1") (pinfunction "1_1") (pintype "passive"))
      (node (ref "C36") (pin "1") (pinfunction "1_1") (pintype "passive"))
      (node (ref "C4") (pin "1") (pinfunction "1_1") (pintype "passive"))
      (node (ref "C5") (pin "1") (pinfunction "1_1") (pintype "passive"))
      (node (ref "C7") (pin "1") (pinfunction "1_1") (pintype "passive"))
      (node (ref "C9") (pin "1") (pinfunction "1_1") (pintype "passive"))
      (node (ref "CF1") (pin "2@1") (pinfunction "2_2@1") (pintype "passive"))
      (node (ref "CF1") (pin "2@2") (pinfunction "2_2@2") (pintype "passive"))
      (node (ref "CF10") (pin "2@1") (pinfunction "2_2@1") (pintype "passive"))
      (node (ref "CF10") (pin "2@2") (pinfunction "2_2@2") (pintype "passive"))
      (node (ref "CF11") (pin "2@1") (pinfunction "2_2@1") (pintype "passive"))
      (node (ref "CF11") (pin "2@2") (pinfunction "2_2@2") (pintype "passive"))
      (node (ref "CF12") (pin "2@1") (pinfunction "2_2@1") (pintype "passive"))
      (node (ref "CF12") (pin "2@2") (pinfunction "2_2@2") (pintype "passive"))
      (node (ref "CF13") (pin "2@1") (pinfunction "2_2@1") (pintype "passive"))
      (node (ref "CF13") (pin "2@2") (pinfunction "2_2@2") (pintype "passive"))
      (node (ref "CF14") (pin "2@1") (pinfunction "2_2@1") (pintype "passive"))
      (node (ref "CF14") (pin "2@2") (pinfunction "2_2@2") (pintype "passive"))
      (node (ref "CF15") (pin "2@1") (pinfunction "2_2@1") (pintype "passive"))
      (node (ref "CF15") (pin "2@2") (pinfunction "2_2@2") (pintype "passive"))
      (node (ref "CF16") (pin "2@1") (pinfunction "2_2@1") (pintype "passive"))
      (node (ref "CF16") (pin "2@2") (pinfunction "2_2@2") (pintype "passive"))
      (node (ref "CF17") (pin "2@1") (pinfunction "2_2@1") (pintype "passive"))
      (node (ref "CF17") (pin "2@2") (pinfunction "2_2@2") (pintype "passive"))
      (node (ref "CF18") (pin "2@1") (pinfunction "2_2@1") (pintype "passive"))
      (node (ref "CF18") (pin "2@2") (pinfunction "2_2@2") (pintype "passive"))
      (node (ref "CF2") (pin "2@1") (pinfunction "2_2@1") (pintype "passive"))
      (node (ref "CF2") (pin "2@2") (pinfunction "2_2@2") (pintype "passive"))
      (node (ref "CF3") (pin "2@1") (pinfunction "2_2@1") (pintype "passive"))
      (node (ref "CF3") (pin "2@2") (pinfunction "2_2@2") (pintype "passive"))
      (node (ref "CF4") (pin "2@1") (pinfunction "2_2@1") (pintype "passive"))
      (node (ref "CF4") (pin "2@2") (pinfunction "2_2@2") (pintype "passive"))
      (node (ref "CF5") (pin "2@1") (pinfunction "2_2@1") (pintype "passive"))
      (node (ref "CF5") (pin "2@2") (pinfunction "2_2@2") (pintype "passive"))
      (node (ref "CF6") (pin "2@1") (pinfunction "2_2@1") (pintype "passive"))
      (node (ref "CF6") (pin "2@2") (pinfunction "2_2@2") (pintype "passive"))
      (node (ref "CF7") (pin "2@1") (pinfunction "2_2@1") (pintype "passive"))
      (node (ref "CF7") (pin "2@2") (pinfunction "2_2@2") (pintype "passive"))
      (node (ref "CF8") (pin "2@1") (pinfunction "2_2@1") (pintype "passive"))
      (node (ref "CF8") (pin "2@2") (pinfunction "2_2@2") (pintype "passive"))
      (node (ref "CF9") (pin "2@1") (pinfunction "2_2@1") (pintype "passive"))
      (node (ref "CF9") (pin "2@2") (pinfunction "2_2@2") (pintype "passive"))
      (node (ref "D1") (pin "A") (pinfunction "A_A") (pintype "passive"))
      (node (ref "IC1") (pin "3") (pinfunction "GND_3") (pintype "passive"))
      (node (ref "IC3") (pin "1") (pinfunction "ADJ_1") (pintype "input"))
      (node (ref "R1") (pin "1") (pinfunction "1_1") (pintype "passive"))
      (node (ref "R11") (pin "2") (pinfunction "2_2") (pintype "passive"))
      (node (ref "R13") (pin "1") (pinfunction "1_1") (pintype "passive"))
      (node (ref "R3") (pin "1") (pinfunction "1_1") (pintype "passive"))
      (node (ref "R6") (pin "2") (pinfunction "2_2") (pintype "passive"))
      (node (ref "R8") (pin "2") (pinfunction "2_2") (pintype "passive"))
      (node (ref "R9") (pin "2") (pinfunction "2_2") (pintype "passive"))
      (node (ref "SV1") (pin "2") (pinfunction "2_2") (pintype "passive"))
      (node (ref "SV2") (pin "2") (pinfunction "2_2") (pintype "passive"))
      (node (ref "SV2") (pin "5") (pinfunction "5_5") (pintype "passive"))
      (node (ref "SV3") (pin "2") (pinfunction "2_2") (pintype "passive"))
      (node (ref "SV3") (pin "5") (pinfunction "5_5") (pintype "passive"))
      (node (ref "SV4") (pin "2") (pinfunction "2_2") (pintype "passive"))
      (node (ref "SV4") (pin "5") (pinfunction "5_5") (pintype "passive"))
      (node (ref "SV5") (pin "2") (pinfunction "2_2") (pintype "passive"))
      (node (ref "SV5") (pin "5") (pinfunction "5_5") (pintype "passive"))
      (node (ref "SV6") (pin "3") (pinfunction "3_3") (pintype "passive"))
      (node (ref "U$1") (pin "2") (pinfunction "DGND_2") (pintype "bidirectional"))
      (node (ref "U$1") (pin "21") (pinfunction "AGND_21") (pintype "bidirectional"))
      (node (ref "U$1") (pin "5") (pinfunction "DGND_5") (pintype "bidirectional"))
      (node (ref "U$1") (pin "6") (pinfunction "DGND_6") (pintype "bidirectional"))
      (node (ref "U$2") (pin "23") (pinfunction "VSS_23") (pintype "bidirectional"))
      (node (ref "U$2") (pin "35") (pinfunction "VSS_35") (pintype "bidirectional"))
      (node (ref "U$2") (pin "47") (pinfunction "VSS_47") (pintype "bidirectional"))
      (node (ref "U$2") (pin "8") (pinfunction "VSSA_8") (pintype "bidirectional"))
      (node (ref "U2*") (pin "4") (pinfunction "A_4") (pintype "passive"))
      (node (ref "U5") (pin "2") (pinfunction "VSS_2") (pintype "power_in"))
    )
    (net (code "27") (name "N$28") (class "Default")
      (node (ref "U$2") (pin "14") (pinfunction "PA4_14") (pintype "bidirectional"))
    )
    (net (code "28") (name "N$29") (class "Default")
      (node (ref "U$2") (pin "13") (pinfunction "PA3_13") (pintype "bidirectional"))
    )
    (net (code "29") (name "NRST") (class "Default")
      (node (ref "SV6") (pin "5") (pinfunction "5_5") (pintype "passive"))
      (node (ref "U$2") (pin "7") (pinfunction "NRST_7") (pintype "bidirectional"))
    )
    (net (code "30") (name "Net-(B72530T300K62-Pad1)") (class "Default")
      (node (ref "B72530T300K62") (pin "1") (pinfunction "1_1") (pintype "passive"))
      (node (ref "F1") (pin "2") (pinfunction "2_2") (pintype "passive"))
      (node (ref "L1") (pin "1") (pinfunction "1_1") (pintype "passive"))
    )
    (net (code "31") (name "Net-(C34-Pad2)") (class "Default")
      (node (ref "C34") (pin "2") (pinfunction "2_2") (pintype "passive"))
      (node (ref "R10") (pin "1") (pinfunction "1_1") (pintype "passive"))
    )
    (net (code "32") (name "Net-(C35-Pad2)") (class "Default")
      (node (ref "C35") (pin "2") (pinfunction "2_2") (pintype "passive"))
      (node (ref "R12") (pin "1") (pinfunction "1_1") (pintype "passive"))
    )
    (net (code "33") (name "Net-(CF9-Pad3)") (class "Default")
      (node (ref "CF9") (pin "3") (pinfunction "3_3") (pintype "passive"))
      (node (ref "R2") (pin "2") (pinfunction "2_2") (pintype "passive"))
    )
    (net (code "34") (name "Net-(CF10-Pad1)") (class "Default")
      (node (ref "CF10") (pin "1") (pinfunction "1_1") (pintype "passive"))
      (node (ref "R3") (pin "2") (pinfunction "2_2") (pintype "passive"))
    )
    (net (code "35") (name "Net-(CF11-Pad3)") (class "Default")
      (node (ref "CF11") (pin "3") (pinfunction "3_3") (pintype "passive"))
      (node (ref "D8") (pin "C") (pinfunction "C_C") (pintype "passive"))
      (node (ref "D9") (pin "A") (pinfunction "A_A") (pintype "passive"))
      (node (ref "R14") (pin "1") (pinfunction "1_1") (pintype "passive"))
    )
    (net (code "36") (name "Net-(CF12-Pad1)") (class "Default")
      (node (ref "CF12") (pin "1") (pinfunction "1_1") (pintype "passive"))
      (node (ref "D8") (pin "A") (pinfunction "A_A") (pintype "passive"))
      (node (ref "D9") (pin "C") (pinfunction "C_C") (pintype "passive"))
      (node (ref "R15") (pin "2") (pinfunction "2_2") (pintype "passive"))
      (node (ref "R6") (pin "1") (pinfunction "1_1") (pintype "passive"))
    )
    (net (code "37") (name "Net-(CF13-Pad3)") (class "Default")
      (node (ref "CF13") (pin "3") (pinfunction "3_3") (pintype "passive"))
      (node (ref "D4") (pin "C") (pinfunction "C_C") (pintype "passive"))
      (node (ref "D5") (pin "A") (pinfunction "A_A") (pintype "passive"))
      (node (ref "R18") (pin "2") (pinfunction "2_2") (pintype "passive"))
    )
    (net (code "38") (name "Net-(CF14-Pad1)") (class "Default")
      (node (ref "CF14") (pin "1") (pinfunction "1_1") (pintype "passive"))
      (node (ref "D4") (pin "A") (pinfunction "A_A") (pintype "passive"))
      (node (ref "D5") (pin "C") (pinfunction "C_C") (pintype "passive"))
      (node (ref "R19") (pin "2") (pinfunction "2_2") (pintype "passive"))
      (node (ref "R8") (pin "1") (pinfunction "1_1") (pintype "passive"))
    )
    (net (code "39") (name "Net-(CF15-Pad3)") (class "Default")
      (node (ref "CF15") (pin "3") (pinfunction "3_3") (pintype "passive"))
      (node (ref "D2") (pin "C") (pinfunction "C_C") (pintype "passive"))
      (node (ref "D3") (pin "A") (pinfunction "A_A") (pintype "passive"))
      (node (ref "R16") (pin "1") (pinfunction "1_1") (pintype "passive"))
    )
    (net (code "40") (name "Net-(CF16-Pad1)") (class "Default")
      (node (ref "CF16") (pin "1") (pinfunction "1_1") (pintype "passive"))
      (node (ref "D2") (pin "A") (pinfunction "A_A") (pintype "passive"))
      (node (ref "D3") (pin "C") (pinfunction "C_C") (pintype "passive"))
      (node (ref "R17") (pin "1") (pinfunction "1_1") (pintype "passive"))
      (node (ref "R9") (pin "1") (pinfunction "1_1") (pintype "passive"))
    )
    (net (code "41") (name "Net-(CF17-Pad3)") (class "Default")
      (node (ref "CF17") (pin "3") (pinfunction "3_3") (pintype "passive"))
      (node (ref "D6") (pin "C") (pinfunction "C_C") (pintype "passive"))
      (node (ref "D7") (pin "A") (pinfunction "A_A") (pintype "passive"))
      (node (ref "R7") (pin "1") (pinfunction "1_1") (pintype "passive"))
    )
    (net (code "42") (name "Net-(CF18-Pad1)") (class "Default")
      (node (ref "CF18") (pin "1") (pinfunction "1_1") (pintype "passive"))
      (node (ref "D6") (pin "A") (pinfunction "A_A") (pintype "passive"))
      (node (ref "D7") (pin "C") (pinfunction "C_C") (pintype "passive"))
      (node (ref "R11") (pin "1") (pinfunction "1_1") (pintype "passive"))
      (node (ref "R5") (pin "1") (pinfunction "1_1") (pintype "passive"))
    )
    (net (code "43") (name "Net-(IC1-VI)") (class "Default")
      (node (ref "C19") (pin "+") (pinfunction "+_+") (pintype "passive"))
      (node (ref "C20") (pin "+") (pinfunction "+_+") (pintype "passive"))
      (node (ref "D1") (pin "C") (pinfunction "C_C") (pintype "passive"))
      (node (ref "IC1") (pin "1") (pinfunction "VI_1") (pintype "input"))
      (node (ref "L1") (pin "2") (pinfunction "2_2") (pintype "passive"))
    )
    (net (code "44") (name "Net-(U$1-A0)") (class "Default")
      (node (ref "CF8") (pin "3") (pinfunction "3_3") (pintype "passive"))
      (node (ref "U$1") (pin "8") (pinfunction "A0_8") (pintype "bidirectional"))
    )
    (net (code "45") (name "Net-(U$1-A1)") (class "Default")
      (node (ref "CF7") (pin "3") (pinfunction "3_3") (pintype "passive"))
      (node (ref "U$1") (pin "7") (pinfunction "A1_7") (pintype "bidirectional"))
    )
    (net (code "46") (name "Net-(U$1-AINN1)") (class "Default")
      (node (ref "C8") (pin "1") (pinfunction "1_1") (pintype "passive"))
      (node (ref "C9") (pin "2") (pinfunction "2_2") (pintype "passive"))
      (node (ref "CF12") (pin "3") (pinfunction "3_3") (pintype "passive"))
      (node (ref "U$1") (pin "12") (pinfunction "AINN1_12") (pintype "bidirectional"))
    )
    (net (code "47") (name "Net-(U$1-AINN2)") (class "Default")
      (node (ref "C11") (pin "1") (pinfunction "1_1") (pintype "passive"))
      (node (ref "C12") (pin "2") (pinfunction "2_2") (pintype "passive"))
      (node (ref "CF14") (pin "3") (pinfunction "3_3") (pintype "passive"))
      (node (ref "U$1") (pin "17") (pinfunction "AINN2_17") (pintype "bidirectional"))
    )
    (net (code "48") (name "Net-(U$1-AINN3)") (class "Default")
      (node (ref "C14") (pin "1") (pinfunction "1_1") (pintype "passive"))
      (node (ref "C15") (pin "2") (pinfunction "2_2") (pintype "passive"))
      (node (ref "CF16") (pin "3") (pinfunction "3_3") (pintype "passive"))
      (node (ref "U$1") (pin "14") (pinfunction "AINN3_14") (pintype "bidirectional"))
    )
    (net (code "49") (name "Net-(U$1-AINN4)") (class "Default")
      (node (ref "C17") (pin "1") (pinfunction "1_1") (pintype "passive"))
      (node (ref "C18") (pin "2") (pinfunction "2_2") (pintype "passive"))
      (node (ref "CF18") (pin "3") (pinfunction "3_3") (pintype "passive"))
      (node (ref "U$1") (pin "15") (pinfunction "AINN4_15") (pintype "bidirectional"))
    )
    (net (code "50") (name "Net-(U$1-AINP1)") (class "Default")
      (node (ref "C7") (pin "2") (pinfunction "2_2") (pintype "passive"))
      (node (ref "C8") (pin "2") (pinfunction "2_2") (pintype "passive"))
      (node (ref "CF11") (pin "1") (pinfunction "1_1") (pintype "passive"))
      (node (ref "U$1") (pin "11") (pinfunction "AINP1_11") (pintype "bidirectional"))
    )
    (net (code "51") (name "Net-(U$1-AINP2)") (class "Default")
      (node (ref "C10") (pin "2") (pinfunction "2_2") (pintype "passive"))
      (node (ref "C11") (pin "2") (pinfunction "2_2") (pintype "passive"))
      (node (ref "CF13") (pin "1") (pinfunction "1_1") (pintype "passive"))
      (node (ref "U$1") (pin "18") (pinfunction "AINP2_18") (pintype "bidirectional"))
    )
    (net (code "52") (name "Net-(U$1-AINP3)") (class "Default")
      (node (ref "C13") (pin "2") (pinfunction "2_2") (pintype "passive"))
      (node (ref "C14") (pin "2") (pinfunction "2_2") (pintype "passive"))
      (node (ref "CF15") (pin "1") (pinfunction "1_1") (pintype "passive"))
      (node (ref "U$1") (pin "13") (pinfunction "AINP3_13") (pintype "bidirectional"))
    )
    (net (code "53") (name "Net-(U$1-AINP4)") (class "Default")
      (node (ref "C16") (pin "2") (pinfunction "2_2") (pintype "passive"))
      (node (ref "C17") (pin "2") (pinfunction "2_2") (pintype "passive"))
      (node (ref "CF17") (pin "1") (pinfunction "1_1") (pintype "passive"))
      (node (ref "U$1") (pin "16") (pinfunction "AINP4_16") (pintype "bidirectional"))
    )
    (net (code "54") (name "Net-(U$1-CAP1)") (class "Default")
      (node (ref "C6") (pin "1") (pinfunction "1_1") (pintype "passive"))
      (node (ref "U$1") (pin "9") (pinfunction "CAP1_9") (pintype "bidirectional"))
    )
    (net (code "55") (name "Net-(U$1-CAP2)") (class "Default")
      (node (ref "C6") (pin "2") (pinfunction "2_2") (pintype "passive"))
      (node (ref "U$1") (pin "10") (pinfunction "CAP2_10") (pintype "bidirectional"))
    )
    (net (code "56") (name "Net-(U$1-CLKIN{slash}XTAL1)") (class "Default")
      (node (ref "R1") (pin "2") (pinfunction "2_2") (pintype "passive"))
      (node (ref "U$1") (pin "3") (pinfunction "CLKIN/XTAL1_3") (pintype "bidirectional"))
    )
    (net (code "57") (name "Net-(U$1-GAIN0)") (class "Default")
      (node (ref "CF4") (pin "3") (pinfunction "3_3") (pintype "passive"))
      (node (ref "U$1") (pin "23") (pinfunction "GAIN0_23") (pintype "bidirectional"))
    )
    (net (code "58") (name "Net-(U$1-GAIN1)") (class "Default")
      (node (ref "CF5") (pin "3") (pinfunction "3_3") (pintype "passive"))
      (node (ref "U$1") (pin "24") (pinfunction "GAIN1_24") (pintype "bidirectional"))
    )
    (net (code "59") (name "Net-(U$1-REFN)") (class "Default")
      (node (ref "C3") (pin "1") (pinfunction "1_1") (pintype "passive"))
      (node (ref "C4") (pin "2") (pinfunction "2_2") (pintype "passive"))
      (node (ref "CF10") (pin "3") (pinfunction "3_3") (pintype "passive"))
      (node (ref "U$1") (pin "19") (pinfunction "REFN_19") (pintype "bidirectional"))
    )
    (net (code "60") (name "Net-(U$1-REFP)") (class "Default")
      (node (ref "C3") (pin "2") (pinfunction "2_2") (pintype "passive"))
      (node (ref "C5") (pin "2") (pinfunction "2_2") (pintype "passive"))
      (node (ref "CF9") (pin "1") (pinfunction "1_1") (pintype "passive"))
      (node (ref "U$1") (pin "20") (pinfunction "REFP_20") (pintype "bidirectional"))
    )
    (net (code "61") (name "Net-(U$1-SCLK)") (class "Default")
      (node (ref "CF2") (pin "3") (pinfunction "3_3") (pintype "passive"))
      (node (ref "U$1") (pin "27") (pinfunction "SCLK_27") (pintype "bidirectional"))
    )
    (net (code "62") (name "Net-(U$1-SPEED)") (class "Default")
      (node (ref "CF3") (pin "3") (pinfunction "3_3") (pintype "passive"))
      (node (ref "U$1") (pin "25") (pinfunction "SPEED_25") (pintype "bidirectional"))
    )
    (net (code "63") (name "Net-(U$1-~{DRDY{slash}}DOUT)") (class "Default")
      (node (ref "CF1") (pin "3") (pinfunction "3_3") (pintype "passive"))
      (node (ref "U$1") (pin "28") (pinfunction "~{DRDY/}DOUT_28") (pintype "bidirectional"))
    )
    (net (code "64") (name "Net-(U$1-~{PDWN})") (class "Default")
      (node (ref "CF6") (pin "3") (pinfunction "3_3") (pintype "passive"))
      (node (ref "U$1") (pin "26") (pinfunction "~{PDWN}_26") (pintype "bidirectional"))
    )
    (net (code "65") (name "Net-(U5-RS)") (class "Default")
      (node (ref "R13") (pin "2") (pinfunction "2_2") (pintype "passive"))
      (node (ref "U5") (pin "8") (pinfunction "RS_8") (pintype "bidirectional"))
    )
    (net (code "66") (name "SWCLK") (class "Default")
      (node (ref "SV6") (pin "2") (pinfunction "2_2") (pintype "passive"))
      (node (ref "U$2") (pin "37") (pinfunction "PA14_37") (pintype "bidirectional"))
    )
    (net (code "67") (name "SWDIO") (class "Default")
      (node (ref "SV6") (pin "4") (pinfunction "4_4") (pintype "passive"))
      (node (ref "U$2") (pin "34") (pinfunction "PA13_34") (pintype "bidirectional"))
    )
    (net (code "68") (name "VDD") (class "Default")
      (node (ref "C21") (pin "+") (pinfunction "+_+") (pintype "passive"))
      (node (ref "C23") (pin "1") (pinfunction "1_1") (pintype "passive"))
      (node (ref "FERRYT") (pin "1") (pinfunction "1_1") (pintype "passive"))
      (node (ref "IC1") (pin "2") (pinfunction "VO_2") (pintype "passive"))
      (node (ref "IC3") (pin "3") (pinfunction "IN_3") (pintype "input"))
    )
    (net (code "69") (name "VOUT") (class "Default")
      (node (ref "R2") (pin "1") (pinfunction "1_1") (pintype "passive"))
      (node (ref "R4") (pin "2") (pinfunction "2_2") (pintype "passive"))
      (node (ref "SV2") (pin "1") (pinfunction "1_1") (pintype "passive"))
      (node (ref "SV3") (pin "1") (pinfunction "1_1") (pintype "passive"))
      (node (ref "SV4") (pin "1") (pinfunction "1_1") (pintype "passive"))
      (node (ref "SV5") (pin "1") (pinfunction "1_1") (pintype "passive"))
      (node (ref "U2*") (pin "8") (pinfunction "C_8") (pintype "passive"))
    )
    (net (code "70") (name "unconnected-(U$1-XTAL2-Pad4)") (class "Default")
      (node (ref "U$1") (pin "4") (pinfunction "XTAL2_4") (pintype "bidirectional"))
    )
    (net (code "71") (name "unconnected-(U$2-PA0-Pad10)") (class "Default")
      (node (ref "U$2") (pin "10") (pinfunction "PA0_10") (pintype "bidirectional"))
    )
    (net (code "72") (name "unconnected-(U$2-PA1-Pad11)") (class "Default")
      (node (ref "U$2") (pin "11") (pinfunction "PA1_11") (pintype "bidirectional"))
    )
    (net (code "73") (name "unconnected-(U$2-PA2-Pad12)") (class "Default")
      (node (ref "U$2") (pin "12") (pinfunction "PA2_12") (pintype "bidirectional"))
    )
    (net (code "74") (name "unconnected-(U$2-PA8-Pad29)") (class "Default")
      (node (ref "U$2") (pin "29") (pinfunction "PA8_29") (pintype "bidirectional"))
    )
    (net (code "75") (name "unconnected-(U$2-PA9-Pad30)") (class "Default")
      (node (ref "U$2") (pin "30") (pinfunction "PA9_30") (pintype "bidirectional"))
    )
    (net (code "76") (name "unconnected-(U$2-PA10-Pad31)") (class "Default")
      (node (ref "U$2") (pin "31") (pinfunction "PA10_31") (pintype "bidirectional"))
    )
    (net (code "77") (name "unconnected-(U$2-PA15-Pad38)") (class "Default")
      (node (ref "U$2") (pin "38") (pinfunction "PA15_38") (pintype "bidirectional"))
    )
    (net (code "78") (name "unconnected-(U$2-PB3-Pad39)") (class "Default")
      (node (ref "U$2") (pin "39") (pinfunction "PB3_39") (pintype "bidirectional"))
    )
    (net (code "79") (name "unconnected-(U$2-PB4-Pad40)") (class "Default")
      (node (ref "U$2") (pin "40") (pinfunction "PB4_40") (pintype "bidirectional"))
    )
    (net (code "80") (name "unconnected-(U$2-PB5-Pad41)") (class "Default")
      (node (ref "U$2") (pin "41") (pinfunction "PB5_41") (pintype "bidirectional"))
    )
    (net (code "81") (name "unconnected-(U$2-PB6-Pad42)") (class "Default")
      (node (ref "U$2") (pin "42") (pinfunction "PB6_42") (pintype "bidirectional"))
    )
    (net (code "82") (name "unconnected-(U$2-PB7-Pad43)") (class "Default")
      (node (ref "U$2") (pin "43") (pinfunction "PB7_43") (pintype "bidirectional"))
    )
    (net (code "83") (name "unconnected-(U$2-PB12-Pad25)") (class "Default")
      (node (ref "U$2") (pin "25") (pinfunction "PB12_25") (pintype "bidirectional"))
    )
    (net (code "84") (name "unconnected-(U$2-PB13-Pad26)") (class "Default")
      (node (ref "U$2") (pin "26") (pinfunction "PB13_26") (pintype "bidirectional"))
    )
    (net (code "85") (name "unconnected-(U$2-PB14-Pad27)") (class "Default")
      (node (ref "U$2") (pin "27") (pinfunction "PB14_27") (pintype "bidirectional"))
    )
    (net (code "86") (name "unconnected-(U$2-PB15-Pad28)") (class "Default")
      (node (ref "U$2") (pin "28") (pinfunction "PB15_28") (pintype "bidirectional"))
    )
    (net (code "87") (name "unconnected-(U$2-PC13-Pad2)") (class "Default")
      (node (ref "U$2") (pin "2") (pinfunction "PC13_2") (pintype "bidirectional"))
    )
    (net (code "88") (name "unconnected-(U$2-PC14-Pad3)") (class "Default")
      (node (ref "U$2") (pin "3") (pinfunction "PC14_3") (pintype "bidirectional"))
    )
    (net (code "89") (name "unconnected-(U$2-PC15-Pad4)") (class "Default")
      (node (ref "U$2") (pin "4") (pinfunction "PC15_4") (pintype "bidirectional"))
    )
    (net (code "90") (name "unconnected-(U$2-PF0-OSC-Pad5)") (class "Default")
      (node (ref "U$2") (pin "5") (pinfunction "PF0-OSC_5") (pintype "bidirectional"))
    )
    (net (code "91") (name "unconnected-(U$2-PF1-OSC-Pad6)") (class "Default")
      (node (ref "U$2") (pin "6") (pinfunction "PF1-OSC_6") (pintype "bidirectional"))
    )
    (net (code "92") (name "unconnected-(U$2-PF11-Pad44)") (class "Default")
      (node (ref "U$2") (pin "44") (pinfunction "PF11_44") (pintype "bidirectional"))
    )
    (net (code "93") (name "unconnected-(U5-VREF-Pad5)") (class "Default")
      (node (ref "U5") (pin "5") (pinfunction "VREF_5") (pintype "bidirectional"))
    )
  )
)
